# BioMod.net
KiCad netlist of a schematic drawn in EAGLE
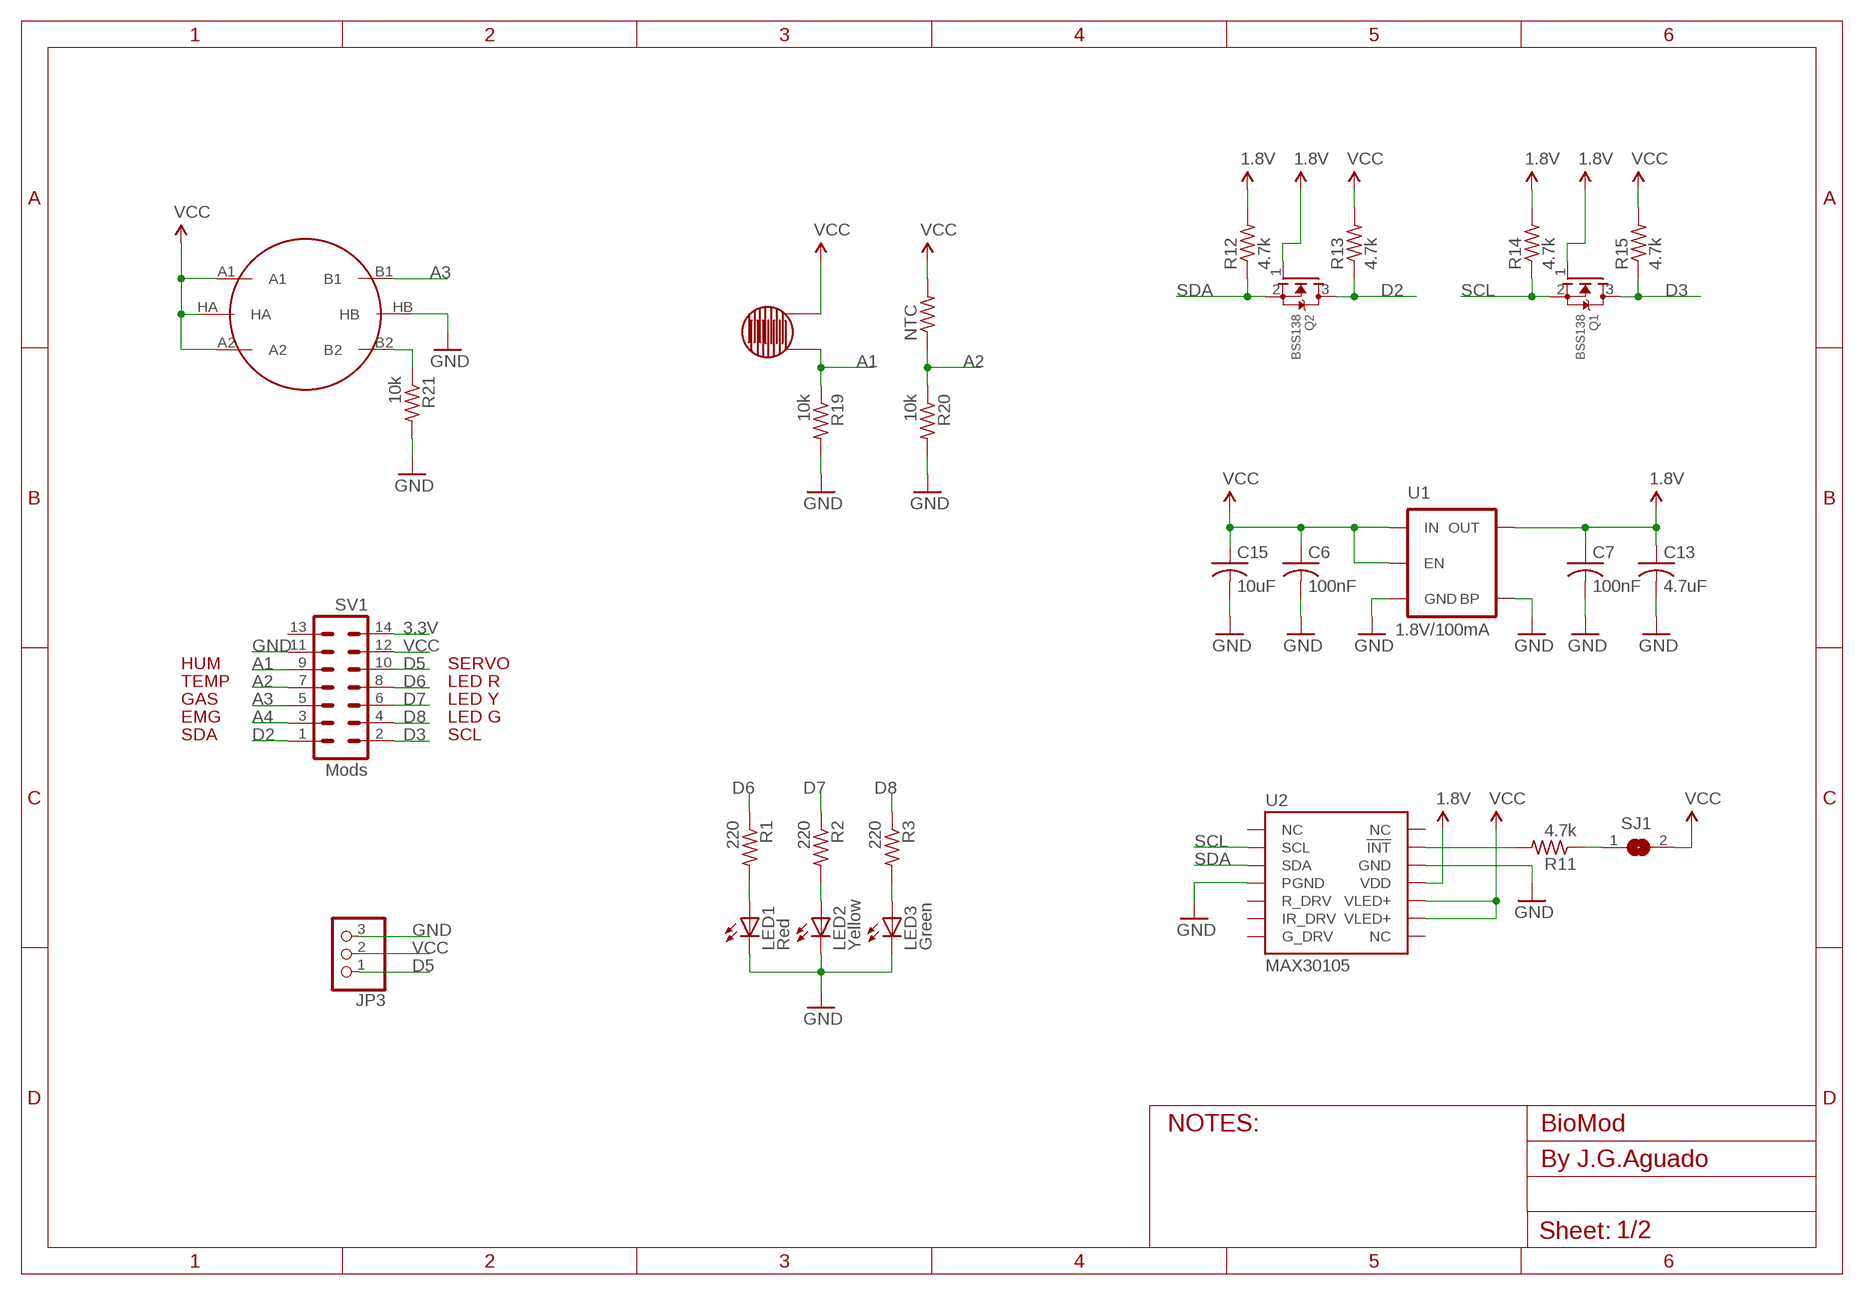
[diagram p0: schematic, sheet 1]
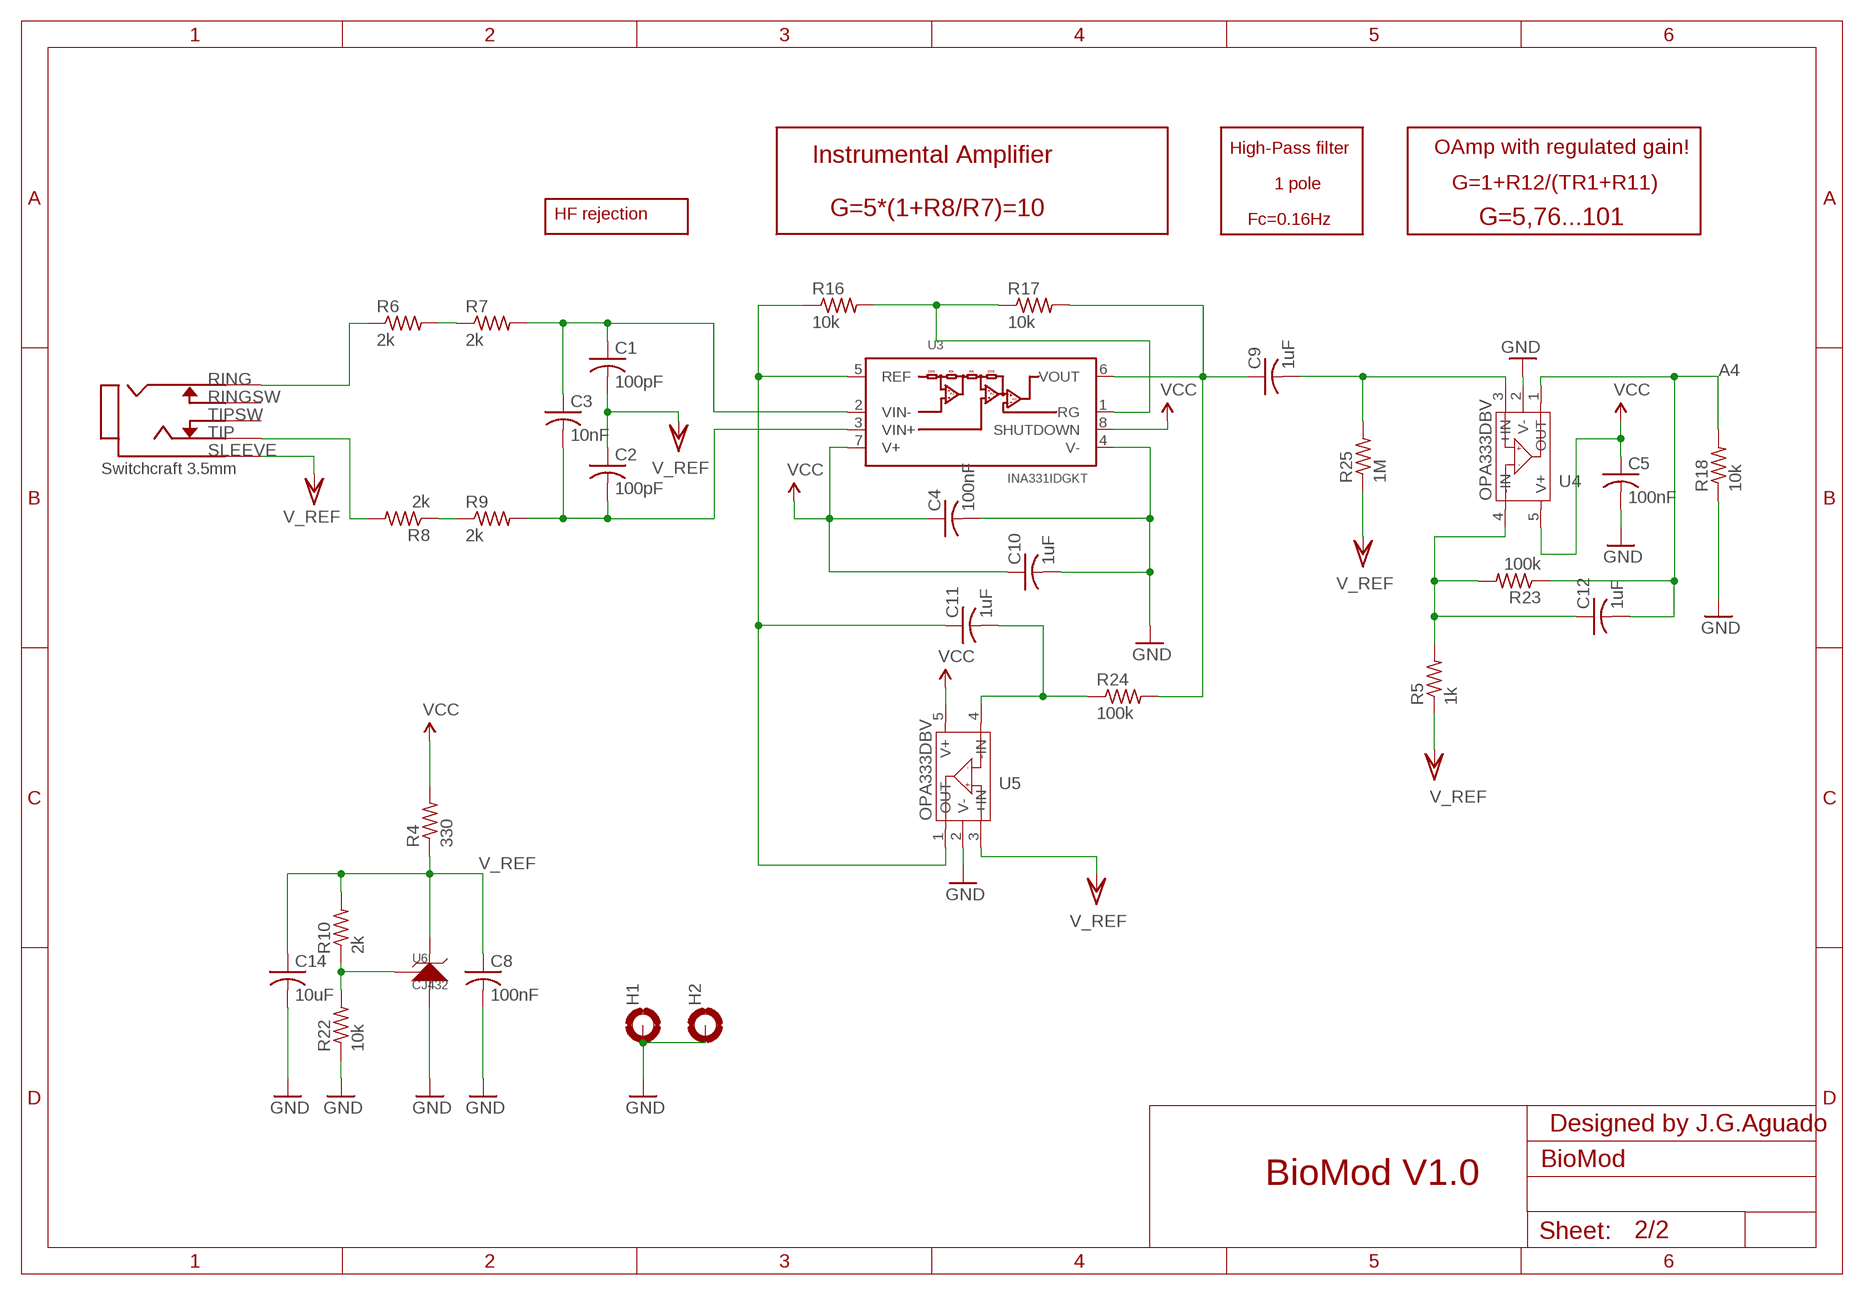
[diagram p1: schematic, sheet 2]

(export (version "E")
  (design (tool "Eeschema 10.0.6"))
  (components
    (comp (ref "C6")
      (value "100nF")
      (footprint "eagle-import:C1206")
      (libsource (lib "eagle-import") (part "C-USC1206"))
    )
    (comp (ref "C7")
      (value "100nF")
      (footprint "eagle-import:C1206")
      (libsource (lib "eagle-import") (part "C-USC1206"))
    )
    (comp (ref "C13")
      (value "4.7uF")
      (footprint "eagle-import:C1206")
      (libsource (lib "eagle-import") (part "C-USC1206"))
    )
    (comp (ref "C15")
      (value "10uF")
      (footprint "eagle-import:C1206")
      (libsource (lib "eagle-import") (part "C-USC1206"))
    )
    (comp (ref "JP3")
      (value "PINHD-1X3")
      (footprint "eagle-import:1X03")
      (libsource (lib "eagle-import") (part "PINHD-1X3"))
    )
    (comp (ref "LED1")
      (value "Red")
      (footprint "eagle-import:1206")
      (libsource (lib "eagle-import") (part "LEDSMT1206"))
    )
    (comp (ref "LED2")
      (value "Yellow")
      (footprint "eagle-import:1206")
      (libsource (lib "eagle-import") (part "LEDSMT1206"))
    )
    (comp (ref "LED3")
      (value "Green")
      (footprint "eagle-import:1206")
      (libsource (lib "eagle-import") (part "LEDSMT1206"))
    )
    (comp (ref "NTC")
      (value "R-US_R1206")
      (footprint "eagle-import:R1206")
      (libsource (lib "eagle-import") (part "R-US_R1206"))
    )
    (comp (ref "Q1")
      (value "BSS138")
      (footprint "eagle-import:SOT23")
      (libsource (lib "eagle-import") (part "MOSFET-NREFLOW"))
    )
    (comp (ref "Q2")
      (value "BSS138")
      (footprint "eagle-import:SOT23")
      (libsource (lib "eagle-import") (part "MOSFET-NREFLOW"))
    )
    (comp (ref "R1")
      (value "220")
      (footprint "eagle-import:R1206")
      (libsource (lib "eagle-import") (part "resistor_R-US_R1206"))
    )
    (comp (ref "R2")
      (value "220")
      (footprint "eagle-import:R1206")
      (libsource (lib "eagle-import") (part "resistor_R-US_R1206"))
    )
    (comp (ref "R3")
      (value "220")
      (footprint "eagle-import:R1206")
      (libsource (lib "eagle-import") (part "resistor_R-US_R1206"))
    )
    (comp (ref "R11")
      (value "4.7k")
      (footprint "eagle-import:R1206")
      (libsource (lib "eagle-import") (part "resistor_R-US_R1206"))
    )
    (comp (ref "R12")
      (value "4.7k")
      (footprint "eagle-import:R1206")
      (libsource (lib "eagle-import") (part "resistor_R-US_R1206"))
    )
    (comp (ref "R13")
      (value "4.7k")
      (footprint "eagle-import:R1206")
      (libsource (lib "eagle-import") (part "resistor_R-US_R1206"))
    )
    (comp (ref "R14")
      (value "4.7k")
      (footprint "eagle-import:R1206")
      (libsource (lib "eagle-import") (part "resistor_R-US_R1206"))
    )
    (comp (ref "R15")
      (value "4.7k")
      (footprint "eagle-import:R1206")
      (libsource (lib "eagle-import") (part "resistor_R-US_R1206"))
    )
    (comp (ref "R19")
      (value "10k")
      (footprint "eagle-import:R1206")
      (libsource (lib "eagle-import") (part "resistor_R-US_R1206"))
    )
    (comp (ref "R20")
      (value "10k")
      (footprint "eagle-import:R1206")
      (libsource (lib "eagle-import") (part "resistor_R-US_R1206"))
    )
    (comp (ref "R21")
      (value "10k")
      (footprint "eagle-import:R1206")
      (libsource (lib "eagle-import") (part "resistor_R-US_R1206"))
    )
    (comp (ref "SJ1") (value "SJ") (footprint "eagle-import:SJ") (libsource (lib "eagle-import") (part "SJ")))
    (comp (ref "SNG")
      (value "METHANE_SENSOR")
      (footprint "eagle-import:MQ-3")
      (libsource (lib "eagle-import") (part "METHANE_SENSOR"))
    )
    (comp (ref "SV1")
      (value "Mods")
      (footprint "eagle-import:MA07-2")
      (libsource (lib "eagle-import") (part "MA07-2"))
    )
    (comp (ref "U$16")
      (value "RESISTIVE_SENSOR_PAD")
      (footprint "eagle-import:RESISTIVE_SENSOR_PAD")
      (libsource (lib "eagle-import") (part "RESISTIVE_SENSOR_PAD"))
    )
    (comp (ref "U1")
      (value "1.8V/100mA")
      (footprint "eagle-import:SC70")
      (libsource (lib "eagle-import") (part "V_REG_SP62141.8V"))
    )
    (comp (ref "U2")
      (value "MAX30105")
      (footprint "eagle-import:OLGA-14")
      (libsource (lib "eagle-import") (part "MAX30105SMD"))
    )
    (comp (ref "C1")
      (value "100pF")
      (footprint "eagle-import:C1206")
      (libsource (lib "eagle-import") (part "C-USC1206"))
    )
    (comp (ref "C2")
      (value "100pF")
      (footprint "eagle-import:C1206")
      (libsource (lib "eagle-import") (part "C-USC1206"))
    )
    (comp (ref "C3")
      (value "10nF")
      (footprint "eagle-import:C1206")
      (libsource (lib "eagle-import") (part "C-USC1206"))
    )
    (comp (ref "C4")
      (value "100nF")
      (footprint "eagle-import:C1206")
      (libsource (lib "eagle-import") (part "C-USC1206"))
    )
    (comp (ref "C5")
      (value "100nF")
      (footprint "eagle-import:C1206")
      (libsource (lib "eagle-import") (part "C-USC1206"))
    )
    (comp (ref "C8")
      (value "100nF")
      (footprint "eagle-import:C1206")
      (libsource (lib "eagle-import") (part "C-USC1206"))
    )
    (comp (ref "C9")
      (value "1uF")
      (footprint "eagle-import:C1206")
      (libsource (lib "eagle-import") (part "C-USC1206"))
    )
    (comp (ref "C10")
      (value "1uF")
      (footprint "eagle-import:C1206")
      (libsource (lib "eagle-import") (part "C-USC1206"))
    )
    (comp (ref "C11")
      (value "1uF")
      (footprint "eagle-import:C1206")
      (libsource (lib "eagle-import") (part "C-USC1206"))
    )
    (comp (ref "C12")
      (value "1uF")
      (footprint "eagle-import:C1206")
      (libsource (lib "eagle-import") (part "C-USC1206"))
    )
    (comp (ref "C14")
      (value "10uF")
      (footprint "eagle-import:C1206")
      (libsource (lib "eagle-import") (part "C-USC1206"))
    )
    (comp (ref "H1")
      (value "MOUNT-PAD-ROUND3.2")
      (footprint "eagle-import:3,2-PAD")
      (libsource (lib "eagle-import") (part "MOUNT-PAD-ROUND3.2"))
    )
    (comp (ref "H2")
      (value "MOUNT-PAD-ROUND3.2")
      (footprint "eagle-import:3,2-PAD")
      (libsource (lib "eagle-import") (part "MOUNT-PAD-ROUND3.2"))
    )
    (comp (ref "JC1")
      (value "SWTCHCRFT_3.5JACK5-JACK-SMD")
      (footprint "eagle-import:4-JACK-SMD")
      (libsource (lib "eagle-import") (part "SWTCHCRFT_3.5JACK5-JACK-SMD"))
    )
    (comp (ref "R4")
      (value "330")
      (footprint "eagle-import:R1206")
      (libsource (lib "eagle-import") (part "resistor_R-US_R1206"))
    )
    (comp (ref "R5")
      (value "1k")
      (footprint "eagle-import:R1206")
      (libsource (lib "eagle-import") (part "resistor_R-US_R1206"))
    )
    (comp (ref "R6")
      (value "2k")
      (footprint "eagle-import:R1206")
      (libsource (lib "eagle-import") (part "resistor_R-US_R1206"))
    )
    (comp (ref "R7")
      (value "2k")
      (footprint "eagle-import:R1206")
      (libsource (lib "eagle-import") (part "resistor_R-US_R1206"))
    )
    (comp (ref "R8")
      (value "2k")
      (footprint "eagle-import:R1206")
      (libsource (lib "eagle-import") (part "resistor_R-US_R1206"))
    )
    (comp (ref "R9")
      (value "2k")
      (footprint "eagle-import:R1206")
      (libsource (lib "eagle-import") (part "resistor_R-US_R1206"))
    )
    (comp (ref "R10")
      (value "2k")
      (footprint "eagle-import:R1206")
      (libsource (lib "eagle-import") (part "resistor_R-US_R1206"))
    )
    (comp (ref "R16")
      (value "10k")
      (footprint "eagle-import:R1206")
      (libsource (lib "eagle-import") (part "resistor_R-US_R1206"))
    )
    (comp (ref "R17")
      (value "10k")
      (footprint "eagle-import:R1206")
      (libsource (lib "eagle-import") (part "resistor_R-US_R1206"))
    )
    (comp (ref "R18")
      (value "10k")
      (footprint "eagle-import:R1206")
      (libsource (lib "eagle-import") (part "resistor_R-US_R1206"))
    )
    (comp (ref "R22")
      (value "10k")
      (footprint "eagle-import:R1206")
      (libsource (lib "eagle-import") (part "resistor_R-US_R1206"))
    )
    (comp (ref "R23")
      (value "100k")
      (footprint "eagle-import:R1206")
      (libsource (lib "eagle-import") (part "resistor_R-US_R1206"))
    )
    (comp (ref "R24")
      (value "100k")
      (footprint "eagle-import:R1206")
      (libsource (lib "eagle-import") (part "resistor_R-US_R1206"))
    )
    (comp (ref "R25")
      (value "1M")
      (footprint "eagle-import:R1206")
      (libsource (lib "eagle-import") (part "resistor_R-US_R1206"))
    )
    (comp (ref "U3")
      (value "INA331IDGKT")
      (footprint "eagle-import:MSOP-8")
      (libsource (lib "eagle-import") (part "INA331EA"))
    )
    (comp (ref "U4")
      (value "OPA333DBV")
      (footprint "eagle-import:SOT23-5")
      (libsource (lib "eagle-import") (part "OPA333DBV"))
    )
    (comp (ref "U5")
      (value "OPA333DBV")
      (footprint "eagle-import:SOT23-5")
      (libsource (lib "eagle-import") (part "OPA333DBV"))
    )
    (comp (ref "U6")
      (value "CJ432")
      (footprint "eagle-import:SOT23")
      (libsource (lib "eagle-import") (part "REFERENCE-SOURCE"))
    )
  )
  (nets
    (net (code "1") (name "1.8V") (class "Default")
      (node (ref "C13") (pin "1") (pinfunction "1_1") (pintype "passive"))
      (node (ref "C7") (pin "1") (pinfunction "1_1") (pintype "passive"))
      (node (ref "Q1") (pin "1") (pinfunction "G_1") (pintype "bidirectional"))
      (node (ref "Q2") (pin "1") (pinfunction "G_1") (pintype "bidirectional"))
      (node (ref "R12") (pin "2") (pinfunction "2_2") (pintype "passive"))
      (node (ref "R14") (pin "2") (pinfunction "2_2") (pintype "passive"))
      (node (ref "U1") (pin "5") (pinfunction "OUT_5") (pintype "passive"))
      (node (ref "U2") (pin "11") (pinfunction "VDD_11") (pintype "bidirectional"))
    )
    (net (code "2") (name "3.3V") (class "Default")
      (node (ref "SV1") (pin "14") (pinfunction "14_14") (pintype "passive"))
    )
    (net (code "3") (name "A1") (class "Default")
      (node (ref "R19") (pin "1") (pinfunction "1_1") (pintype "passive"))
      (node (ref "SV1") (pin "9") (pinfunction "9_9") (pintype "passive"))
      (node (ref "U$16") (pin "1") (pinfunction "1_1") (pintype "bidirectional"))
    )
    (net (code "4") (name "A2") (class "Default")
      (node (ref "NTC") (pin "1") (pinfunction "1_1") (pintype "passive"))
      (node (ref "R20") (pin "1") (pinfunction "1_1") (pintype "passive"))
      (node (ref "SV1") (pin "7") (pinfunction "7_7") (pintype "passive"))
    )
    (net (code "5") (name "A3") (class "Default")
      (node (ref "SNG") (pin "B1") (pinfunction "B1_B1") (pintype "bidirectional"))
      (node (ref "SV1") (pin "5") (pinfunction "5_5") (pintype "passive"))
    )
    (net (code "6") (name "A4") (class "Default")
      (node (ref "C12") (pin "2") (pinfunction "2_2") (pintype "passive"))
      (node (ref "R18") (pin "2") (pinfunction "2_2") (pintype "passive"))
      (node (ref "R23") (pin "1") (pinfunction "1_1") (pintype "passive"))
      (node (ref "SV1") (pin "3") (pinfunction "3_3") (pintype "passive"))
      (node (ref "U4") (pin "1") (pinfunction "OUT_1") (pintype "bidirectional"))
    )
    (net (code "7") (name "D2") (class "Default")
      (node (ref "Q2") (pin "3") (pinfunction "D_3") (pintype "bidirectional"))
      (node (ref "R13") (pin "1") (pinfunction "1_1") (pintype "passive"))
      (node (ref "SV1") (pin "1") (pinfunction "1_1") (pintype "passive"))
    )
    (net (code "8") (name "D3") (class "Default")
      (node (ref "Q1") (pin "3") (pinfunction "D_3") (pintype "bidirectional"))
      (node (ref "R15") (pin "1") (pinfunction "1_1") (pintype "passive"))
      (node (ref "SV1") (pin "2") (pinfunction "2_2") (pintype "passive"))
    )
    (net (code "9") (name "D5") (class "Default")
      (node (ref "JP3") (pin "1") (pinfunction "1_1") (pintype "passive"))
      (node (ref "SV1") (pin "10") (pinfunction "10_10") (pintype "passive"))
    )
    (net (code "10") (name "D6") (class "Default")
      (node (ref "R1") (pin "1") (pinfunction "1_1") (pintype "passive"))
      (node (ref "SV1") (pin "8") (pinfunction "8_8") (pintype "passive"))
    )
    (net (code "11") (name "D7") (class "Default")
      (node (ref "R2") (pin "1") (pinfunction "1_1") (pintype "passive"))
      (node (ref "SV1") (pin "6") (pinfunction "6_6") (pintype "passive"))
    )
    (net (code "12") (name "D8") (class "Default")
      (node (ref "R3") (pin "1") (pinfunction "1_1") (pintype "passive"))
      (node (ref "SV1") (pin "4") (pinfunction "4_4") (pintype "passive"))
    )
    (net (code "13") (name "GND") (class "Default")
      (node (ref "C10") (pin "2") (pinfunction "2_2") (pintype "passive"))
      (node (ref "C13") (pin "2") (pinfunction "2_2") (pintype "passive"))
      (node (ref "C14") (pin "2") (pinfunction "2_2") (pintype "passive"))
      (node (ref "C15") (pin "2") (pinfunction "2_2") (pintype "passive"))
      (node (ref "C4") (pin "2") (pinfunction "2_2") (pintype "passive"))
      (node (ref "C5") (pin "2") (pinfunction "2_2") (pintype "passive"))
      (node (ref "C6") (pin "2") (pinfunction "2_2") (pintype "passive"))
      (node (ref "C7") (pin "2") (pinfunction "2_2") (pintype "passive"))
      (node (ref "C8") (pin "2") (pinfunction "2_2") (pintype "passive"))
      (node (ref "H1") (pin "B3,2") (pinfunction "MOUNT_B3,2") (pintype "passive"))
      (node (ref "H2") (pin "B3,2") (pinfunction "MOUNT_B3,2") (pintype "passive"))
      (node (ref "JP3") (pin "3") (pinfunction "3_3") (pintype "passive"))
      (node (ref "LED1") (pin "C") (pinfunction "C_C") (pintype "passive"))
      (node (ref "LED2") (pin "C") (pinfunction "C_C") (pintype "passive"))
      (node (ref "LED3") (pin "C") (pinfunction "C_C") (pintype "passive"))
      (node (ref "R18") (pin "1") (pinfunction "1_1") (pintype "passive"))
      (node (ref "R19") (pin "2") (pinfunction "2_2") (pintype "passive"))
      (node (ref "R20") (pin "2") (pinfunction "2_2") (pintype "passive"))
      (node (ref "R21") (pin "2") (pinfunction "2_2") (pintype "passive"))
      (node (ref "R22") (pin "1") (pinfunction "1_1") (pintype "passive"))
      (node (ref "SNG") (pin "HB") (pinfunction "HB_HB") (pintype "bidirectional"))
      (node (ref "SV1") (pin "11") (pinfunction "11_11") (pintype "passive"))
      (node (ref "U1") (pin "2") (pinfunction "GND_2") (pintype "input"))
      (node (ref "U1") (pin "4") (pinfunction "BP_4") (pintype "input"))
      (node (ref "U2") (pin "12") (pinfunction "GND_12") (pintype "bidirectional"))
      (node (ref "U2") (pin "4") (pinfunction "PGND_4") (pintype "bidirectional"))
      (node (ref "U3") (pin "4") (pinfunction "V-_4") (pintype "power_in"))
      (node (ref "U4") (pin "2") (pinfunction "V-_2") (pintype "bidirectional"))
      (node (ref "U5") (pin "2") (pinfunction "V-_2") (pintype "bidirectional"))
      (node (ref "U6") (pin "3") (pinfunction "A_3") (pintype "bidirectional"))
    )
    (net (code "14") (name "Net-(JC1-Pad2)") (class "Default")
      (node (ref "JC1") (pin "2") (pinfunction "2_2") (pintype "bidirectional"))
      (node (ref "R6") (pin "1") (pinfunction "1_1") (pintype "passive"))
    )
    (net (code "15") (name "Net-(JC1-Pad3)") (class "Default")
      (node (ref "JC1") (pin "3") (pinfunction "3_3") (pintype "bidirectional"))
      (node (ref "R8") (pin "2") (pinfunction "2_2") (pintype "passive"))
    )
    (net (code "16") (name "Net-(LED1-PadA)") (class "Default")
      (node (ref "LED1") (pin "A") (pinfunction "A_A") (pintype "passive"))
      (node (ref "R1") (pin "2") (pinfunction "2_2") (pintype "passive"))
    )
    (net (code "17") (name "Net-(LED2-PadA)") (class "Default")
      (node (ref "LED2") (pin "A") (pinfunction "A_A") (pintype "passive"))
      (node (ref "R2") (pin "2") (pinfunction "2_2") (pintype "passive"))
    )
    (net (code "18") (name "Net-(LED3-PadA)") (class "Default")
      (node (ref "LED3") (pin "A") (pinfunction "A_A") (pintype "passive"))
      (node (ref "R3") (pin "2") (pinfunction "2_2") (pintype "passive"))
    )
    (net (code "19") (name "Net-(R6-Pad2)") (class "Default")
      (node (ref "R6") (pin "2") (pinfunction "2_2") (pintype "passive"))
      (node (ref "R7") (pin "1") (pinfunction "1_1") (pintype "passive"))
    )
    (net (code "20") (name "Net-(R8-Pad1)") (class "Default")
      (node (ref "R8") (pin "1") (pinfunction "1_1") (pintype "passive"))
      (node (ref "R9") (pin "1") (pinfunction "1_1") (pintype "passive"))
    )
    (net (code "21") (name "Net-(R11-Pad1)") (class "Default")
      (node (ref "R11") (pin "1") (pinfunction "1_1") (pintype "passive"))
      (node (ref "SJ1") (pin "1") (pinfunction "1_1") (pintype "passive"))
    )
    (net (code "22") (name "Net-(R21-Pad1)") (class "Default")
      (node (ref "R21") (pin "1") (pinfunction "1_1") (pintype "passive"))
      (node (ref "SNG") (pin "B2") (pinfunction "B2_B2") (pintype "bidirectional"))
    )
    (net (code "23") (name "Net-(U2-~{INT})") (class "Default")
      (node (ref "R11") (pin "2") (pinfunction "2_2") (pintype "passive"))
      (node (ref "U2") (pin "13") (pinfunction "~{INT}_13") (pintype "bidirectional"))
    )
    (net (code "24") (name "Net-(U3-REF)") (class "Default")
      (node (ref "C11") (pin "1") (pinfunction "1_1") (pintype "passive"))
      (node (ref "R16") (pin "1") (pinfunction "1_1") (pintype "passive"))
      (node (ref "U3") (pin "5") (pinfunction "REF_5") (pintype "input"))
      (node (ref "U5") (pin "1") (pinfunction "OUT_1") (pintype "bidirectional"))
    )
    (net (code "25") (name "Net-(U3-RG)") (class "Default")
      (node (ref "R16") (pin "2") (pinfunction "2_2") (pintype "passive"))
      (node (ref "R17") (pin "1") (pinfunction "1_1") (pintype "passive"))
      (node (ref "U3") (pin "1") (pinfunction "RG_1") (pintype "input"))
    )
    (net (code "26") (name "Net-(U3-VIN+)") (class "Default")
      (node (ref "C2") (pin "2") (pinfunction "2_2") (pintype "passive"))
      (node (ref "C3") (pin "2") (pinfunction "2_2") (pintype "passive"))
      (node (ref "R9") (pin "2") (pinfunction "2_2") (pintype "passive"))
      (node (ref "U3") (pin "3") (pinfunction "VIN+_3") (pintype "input"))
    )
    (net (code "27") (name "Net-(U3-VIN-)") (class "Default")
      (node (ref "C1") (pin "1") (pinfunction "1_1") (pintype "passive"))
      (node (ref "C3") (pin "1") (pinfunction "1_1") (pintype "passive"))
      (node (ref "R7") (pin "2") (pinfunction "2_2") (pintype "passive"))
      (node (ref "U3") (pin "2") (pinfunction "VIN-_2") (pintype "input"))
    )
    (net (code "28") (name "Net-(U3-VOUT)") (class "Default")
      (node (ref "C9") (pin "1") (pinfunction "1_1") (pintype "passive"))
      (node (ref "R17") (pin "2") (pinfunction "2_2") (pintype "passive"))
      (node (ref "R24") (pin "2") (pinfunction "2_2") (pintype "passive"))
      (node (ref "U3") (pin "6") (pinfunction "VOUT_6") (pintype "output"))
    )
    (net (code "29") (name "Net-(U4-+IN)") (class "Default")
      (node (ref "C9") (pin "2") (pinfunction "2_2") (pintype "passive"))
      (node (ref "R25") (pin "2") (pinfunction "2_2") (pintype "passive"))
      (node (ref "U4") (pin "3") (pinfunction "+IN_3") (pintype "bidirectional"))
    )
    (net (code "30") (name "Net-(U4--IN)") (class "Default")
      (node (ref "C12") (pin "1") (pinfunction "1_1") (pintype "passive"))
      (node (ref "R23") (pin "2") (pinfunction "2_2") (pintype "passive"))
      (node (ref "R5") (pin "2") (pinfunction "2_2") (pintype "passive"))
      (node (ref "U4") (pin "4") (pinfunction "-IN_4") (pintype "bidirectional"))
    )
    (net (code "31") (name "Net-(U5--IN)") (class "Default")
      (node (ref "C11") (pin "2") (pinfunction "2_2") (pintype "passive"))
      (node (ref "R24") (pin "1") (pinfunction "1_1") (pintype "passive"))
      (node (ref "U5") (pin "4") (pinfunction "-IN_4") (pintype "bidirectional"))
    )
    (net (code "32") (name "Net-(U6-R)") (class "Default")
      (node (ref "R10") (pin "1") (pinfunction "1_1") (pintype "passive"))
      (node (ref "R22") (pin "2") (pinfunction "2_2") (pintype "passive"))
      (node (ref "U6") (pin "1") (pinfunction "R_1") (pintype "bidirectional"))
    )
    (net (code "33") (name "SCL") (class "Default")
      (node (ref "Q1") (pin "2") (pinfunction "S_2") (pintype "bidirectional"))
      (node (ref "R14") (pin "1") (pinfunction "1_1") (pintype "passive"))
      (node (ref "U2") (pin "2") (pinfunction "SCL_2") (pintype "bidirectional"))
    )
    (net (code "34") (name "SDA") (class "Default")
      (node (ref "Q2") (pin "2") (pinfunction "S_2") (pintype "bidirectional"))
      (node (ref "R12") (pin "1") (pinfunction "1_1") (pintype "passive"))
      (node (ref "U2") (pin "3") (pinfunction "SDA_3") (pintype "bidirectional"))
    )
    (net (code "35") (name "VCC") (class "Default")
      (node (ref "C10") (pin "1") (pinfunction "1_1") (pintype "passive"))
      (node (ref "C15") (pin "1") (pinfunction "1_1") (pintype "passive"))
      (node (ref "C4") (pin "1") (pinfunction "1_1") (pintype "passive"))
      (node (ref "C5") (pin "1") (pinfunction "1_1") (pintype "passive"))
      (node (ref "C6") (pin "1") (pinfunction "1_1") (pintype "passive"))
      (node (ref "JP3") (pin "2") (pinfunction "2_2") (pintype "passive"))
      (node (ref "NTC") (pin "2") (pinfunction "2_2") (pintype "passive"))
      (node (ref "R13") (pin "2") (pinfunction "2_2") (pintype "passive"))
      (node (ref "R15") (pin "2") (pinfunction "2_2") (pintype "passive"))
      (node (ref "R4") (pin "2") (pinfunction "2_2") (pintype "passive"))
      (node (ref "SJ1") (pin "2") (pinfunction "2_2") (pintype "passive"))
      (node (ref "SNG") (pin "A1") (pinfunction "A1_A1") (pintype "bidirectional"))
      (node (ref "SNG") (pin "A2") (pinfunction "A2_A2") (pintype "bidirectional"))
      (node (ref "SNG") (pin "HA") (pinfunction "HA_HA") (pintype "bidirectional"))
      (node (ref "SV1") (pin "12") (pinfunction "12_12") (pintype "passive"))
      (node (ref "U$16") (pin "0") (pinfunction "0_0") (pintype "bidirectional"))
      (node (ref "U1") (pin "1") (pinfunction "IN_1") (pintype "input"))
      (node (ref "U1") (pin "3") (pinfunction "EN_3") (pintype "input"))
      (node (ref "U2") (pin "10") (pinfunction "VLED+_10") (pintype "bidirectional"))
      (node (ref "U2") (pin "9") (pinfunction "VLED+_9") (pintype "bidirectional"))
      (node (ref "U3") (pin "7") (pinfunction "V+_7") (pintype "power_in"))
      (node (ref "U3") (pin "8") (pinfunction "SHUTDOWN_8") (pintype "input"))
      (node (ref "U4") (pin "5") (pinfunction "V+_5") (pintype "bidirectional"))
      (node (ref "U5") (pin "5") (pinfunction "V+_5") (pintype "bidirectional"))
    )
    (net (code "36") (name "V_REF") (class "Default")
      (node (ref "C1") (pin "2") (pinfunction "2_2") (pintype "passive"))
      (node (ref "C14") (pin "1") (pinfunction "1_1") (pintype "passive"))
      (node (ref "C2") (pin "1") (pinfunction "1_1") (pintype "passive"))
      (node (ref "C8") (pin "1") (pinfunction "1_1") (pintype "passive"))
      (node (ref "JC1") (pin "1") (pinfunction "1_1") (pintype "bidirectional"))
      (node (ref "R10") (pin "2") (pinfunction "2_2") (pintype "passive"))
      (node (ref "R25") (pin "1") (pinfunction "1_1") (pintype "passive"))
      (node (ref "R4") (pin "1") (pinfunction "1_1") (pintype "passive"))
      (node (ref "R5") (pin "1") (pinfunction "1_1") (pintype "passive"))
      (node (ref "U5") (pin "3") (pinfunction "+IN_3") (pintype "bidirectional"))
      (node (ref "U6") (pin "2") (pinfunction "K_2") (pintype "bidirectional"))
    )
    (net (code "37") (name "unconnected-(JC1-Pad4)") (class "Default")
      (node (ref "JC1") (pin "4") (pinfunction "4_4") (pintype "bidirectional"))
    )
    (net (code "38") (name "unconnected-(JC1-Pad5)") (class "Default")
      (node (ref "JC1") (pin "5") (pinfunction "5_5") (pintype "bidirectional"))
    )
    (net (code "39") (name "unconnected-(SV1-Pad13)") (class "Default")
      (node (ref "SV1") (pin "13") (pinfunction "13_13") (pintype "passive"))
    )
    (net (code "40") (name "unconnected-(U2-G_DRV-Pad7)") (class "Default")
      (node (ref "U2") (pin "7") (pinfunction "G_DRV_7") (pintype "bidirectional"))
    )
    (net (code "41") (name "unconnected-(U2-IR_DRV-Pad6)") (class "Default")
      (node (ref "U2") (pin "6") (pinfunction "IR_DRV_6") (pintype "bidirectional"))
    )
    (net (code "42") (name "unconnected-(U2-NC-Pad1)") (class "Default")
      (node (ref "U2") (pin "1") (pinfunction "NC_1") (pintype "bidirectional"))
    )
    (net (code "43") (name "unconnected-(U2-NC-Pad8)") (class "Default")
      (node (ref "U2") (pin "8") (pinfunction "NC_8") (pintype "bidirectional"))
    )
    (net (code "44") (name "unconnected-(U2-NC-Pad14)") (class "Default")
      (node (ref "U2") (pin "14") (pinfunction "NC_14") (pintype "bidirectional"))
    )
    (net (code "45") (name "unconnected-(U2-R_DRV-Pad5)") (class "Default")
      (node (ref "U2") (pin "5") (pinfunction "R_DRV_5") (pintype "bidirectional"))
    )
  )
)
